# CCjammerRev0_TOP.net
KiCad netlist of a schematic drawn in Altium Designer
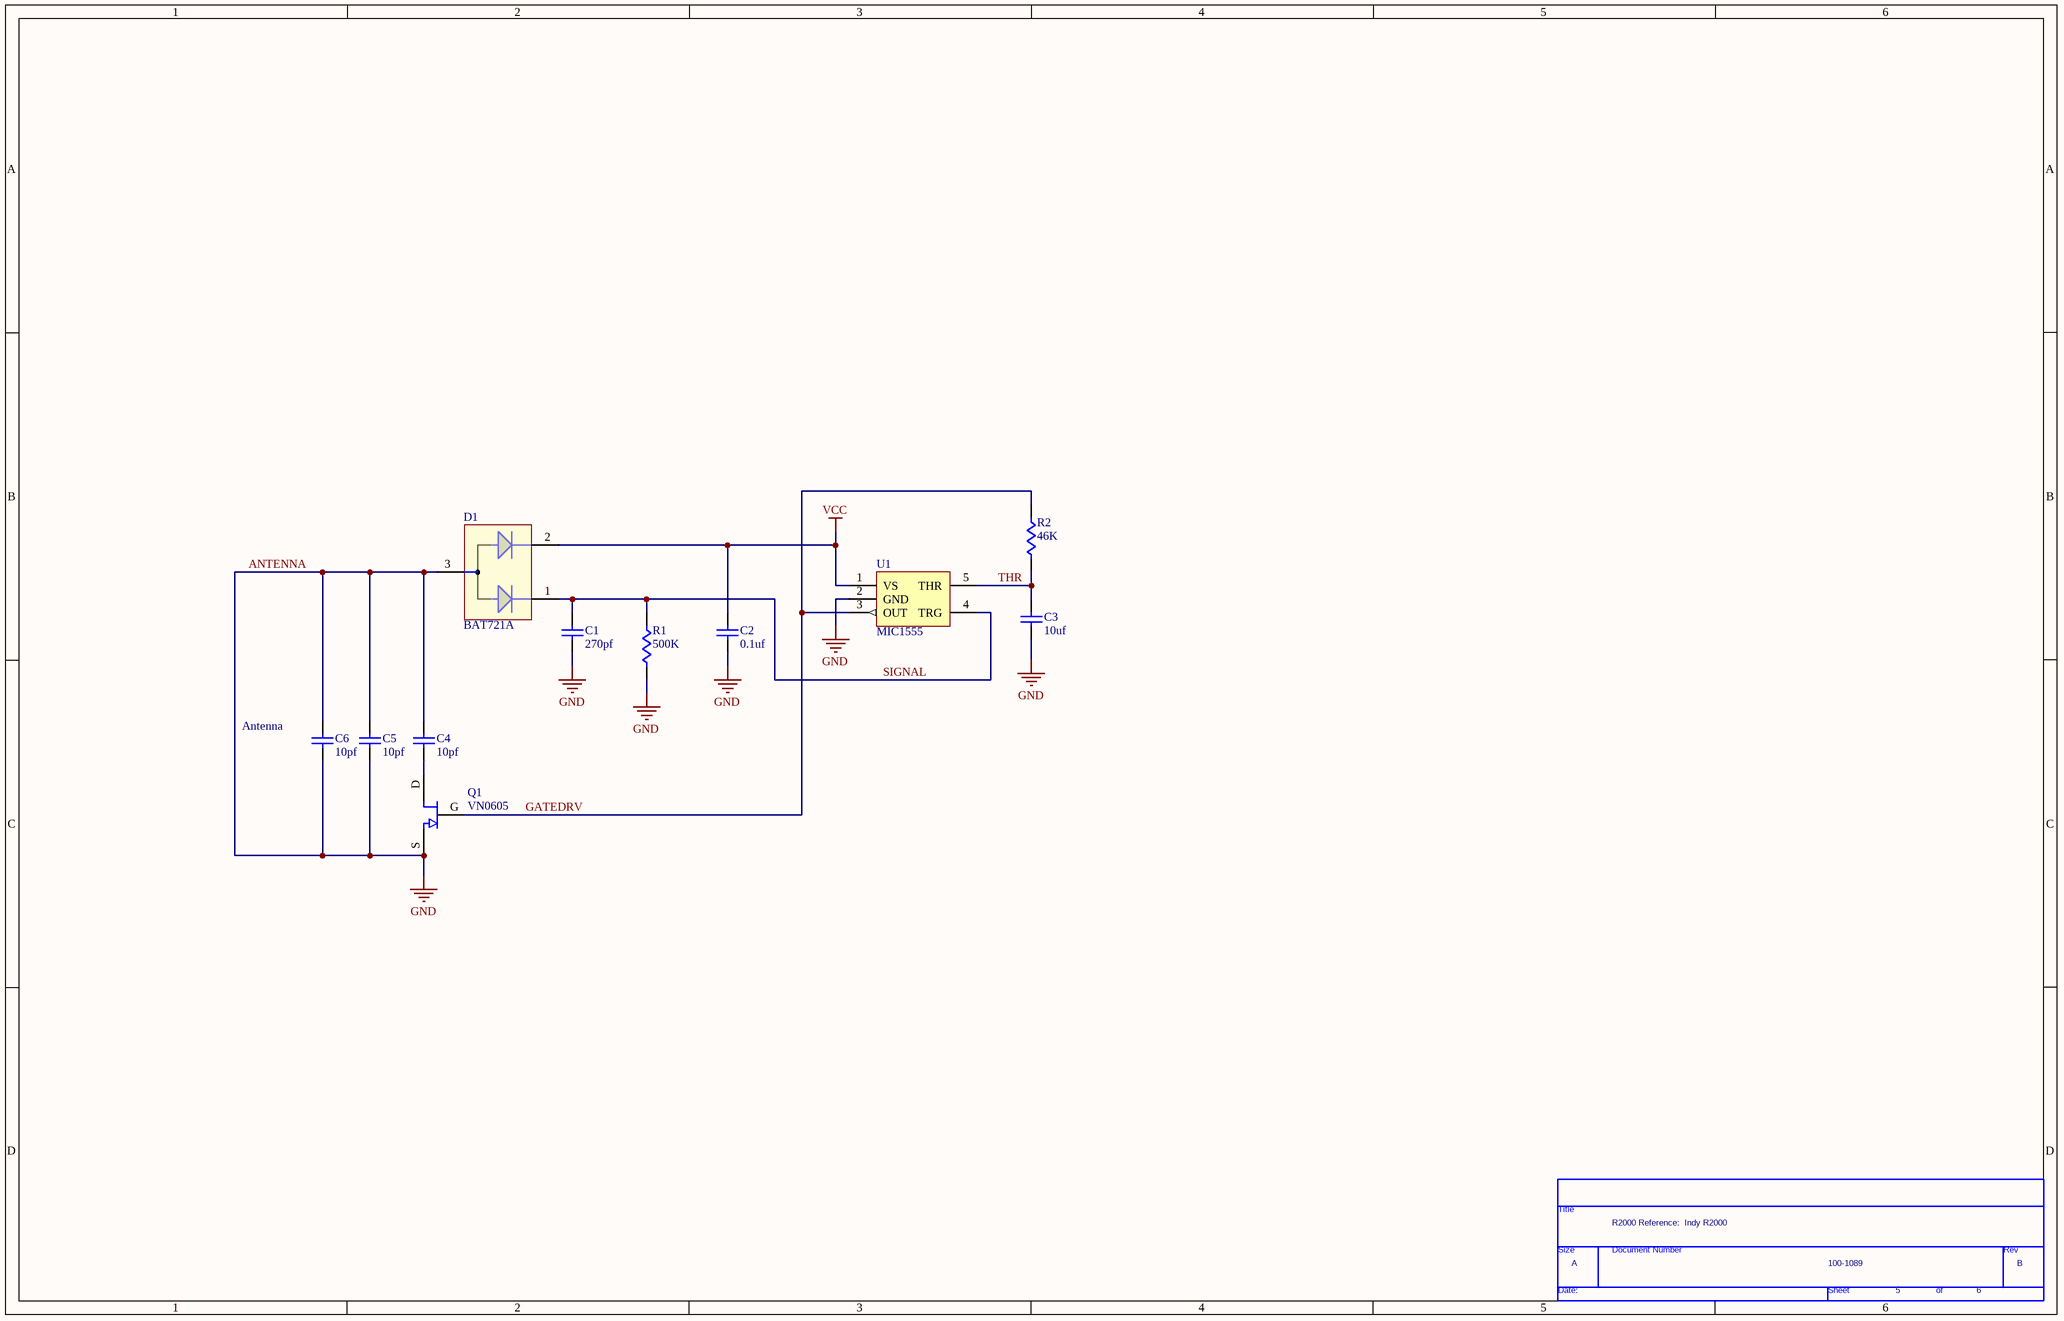
[diagram p0: CCjammerRev0_TOP.SchDoc]

(export (version "E")
  (design (tool "Eeschema 10.0.6"))
  (components
    (comp (ref "*")
      (value "TitleBlock0")
      (fields
        (field (name "PAGE COUNT") "6")
        (field (name "PAGE NUMBER") "5")
        (field (name "PAGE SIZE") "A")
        (field (name "TITLE") "R2000 Reference:  Indy R2000")
        (field (name "REVCODE") "B")
        (field (name "DOC") "100-1089")
      )
      (libsource (lib "*") (part "TitleBlock0"))
    )
    (comp (ref "C1")
      (value "270pf")
      (footprint "0603_072205")
      (description "Capacitor")
      (libsource (lib "Miscellaneous Devices") (part "Cap"))
    )
    (comp (ref "C2")
      (value "0.1uf")
      (footprint "0603_072205")
      (description "Capacitor")
      (fields (field (name "PARTNO") "TMK212BJ475KG-T"))
      (libsource (lib "Miscellaneous Devices") (part "Cap"))
    )
    (comp (ref "C3")
      (value "10uf")
      (footprint "0603_072205")
      (description "Capacitor")
      (libsource (lib "Miscellaneous Devices") (part "Cap"))
    )
    (comp (ref "C4")
      (value "10pf")
      (footprint "0603_072205")
      (description "Capacitor")
      (libsource (lib "Miscellaneous Devices") (part "Cap"))
    )
    (comp (ref "C5")
      (value "10pf")
      (footprint "0603_072205")
      (description "Capacitor")
      (libsource (lib "Miscellaneous Devices") (part "Cap"))
    )
    (comp (ref "C6")
      (value "10pf")
      (footprint "0603_072205")
      (description "Capacitor")
      (libsource (lib "Miscellaneous Devices") (part "Cap"))
    )
    (comp (ref "D1")
      (value "BAT721A")
      (footprint "SOT23_012105")
      (fields (field (name "PARTNO") "BAT721A,215"))
      (libsource (lib "Common") (part "DIODE_DUAL_COM_AN_SOT23"))
    )
    (comp (ref "Q1")
      (value "VN0605")
      (footprint "SOT23 FET_012005")
      (fields (field (name "PARTNO") "VN0605T") (field (name "MFG") "Vishay"))
      (libsource (lib "Common") (part "FET N CHANNEL"))
    )
    (comp (ref "R1")
      (value "500K")
      (footprint "0603_072205")
      (fields (field (name "PARTNO") "RES-0000"))
      (libsource (lib "Discrete") (part "RESISTOR"))
    )
    (comp (ref "R2")
      (value "46K")
      (footprint "0603_072205")
      (fields (field (name "PARTNO") "RES-0000"))
      (libsource (lib "Discrete") (part "RESISTOR"))
    )
    (comp (ref "U1")
      (value "MIC1555")
      (footprint "SOT25_030205")
      (fields (field (name "MFG") "Micrel") (field (name "PARTNO") "MIC1555YM5"))
      (libsource (lib "Common") (part "MIC1555"))
    )
  )
  (nets
    (net (code "1") (name "/GATEDRV") (class "Default")
      (node (ref "Q1") (pin "G") (pinfunction "G_G") (pintype "passive"))
      (node (ref "R2") (pin "2") (pinfunction "2_2") (pintype "passive"))
      (node (ref "U1") (pin "3") (pinfunction "OUT_3") (pintype "output"))
    )
    (net (code "2") (name "/SIGNAL") (class "Default")
      (node (ref "C1") (pin "2") (pinfunction "2_2") (pintype "passive"))
      (node (ref "D1") (pin "1") (pinfunction "1_1") (pintype "passive"))
      (node (ref "R1") (pin "2") (pinfunction "2_2") (pintype "passive"))
      (node (ref "U1") (pin "4") (pinfunction "TRG_4") (pintype "passive"))
    )
    (net (code "3") (name "/THR") (class "Default")
      (node (ref "C3") (pin "2") (pinfunction "2_2") (pintype "passive"))
      (node (ref "R2") (pin "1") (pinfunction "1_1") (pintype "passive"))
      (node (ref "U1") (pin "5") (pinfunction "THR_5") (pintype "passive"))
    )
    (net (code "4") (name "GND") (class "Default")
      (node (ref "C1") (pin "1") (pinfunction "1_1") (pintype "passive"))
      (node (ref "C2") (pin "1") (pinfunction "1_1") (pintype "passive"))
      (node (ref "C3") (pin "1") (pinfunction "1_1") (pintype "passive"))
      (node (ref "C4") (pin "2") (pinfunction "2_2") (pintype "passive"))
      (node (ref "C5") (pin "1") (pinfunction "1_1") (pintype "passive"))
      (node (ref "C5") (pin "2") (pinfunction "2_2") (pintype "passive"))
      (node (ref "C6") (pin "1") (pinfunction "1_1") (pintype "passive"))
      (node (ref "C6") (pin "2") (pinfunction "2_2") (pintype "passive"))
      (node (ref "D1") (pin "3") (pinfunction "AC_3") (pintype "passive"))
      (node (ref "Q1") (pin "S") (pinfunction "S_S") (pintype "passive"))
      (node (ref "R1") (pin "1") (pinfunction "1_1") (pintype "passive"))
      (node (ref "U1") (pin "2") (pinfunction "GND_2") (pintype "power_in"))
    )
    (net (code "5") (name "Net-(C4-Pad1)") (class "Default")
      (node (ref "C4") (pin "1") (pinfunction "1_1") (pintype "passive"))
      (node (ref "Q1") (pin "D") (pinfunction "D_D") (pintype "passive"))
    )
    (net (code "6") (name "VCC") (class "Default")
      (node (ref "C2") (pin "2") (pinfunction "2_2") (pintype "passive"))
      (node (ref "D1") (pin "2") (pinfunction "2_2") (pintype "passive"))
      (node (ref "U1") (pin "1") (pinfunction "VS_1") (pintype "power_in"))
    )
  )
)
